# GecikmeliAnahtar.net
KiCad netlist of a schematic drawn in EAGLE
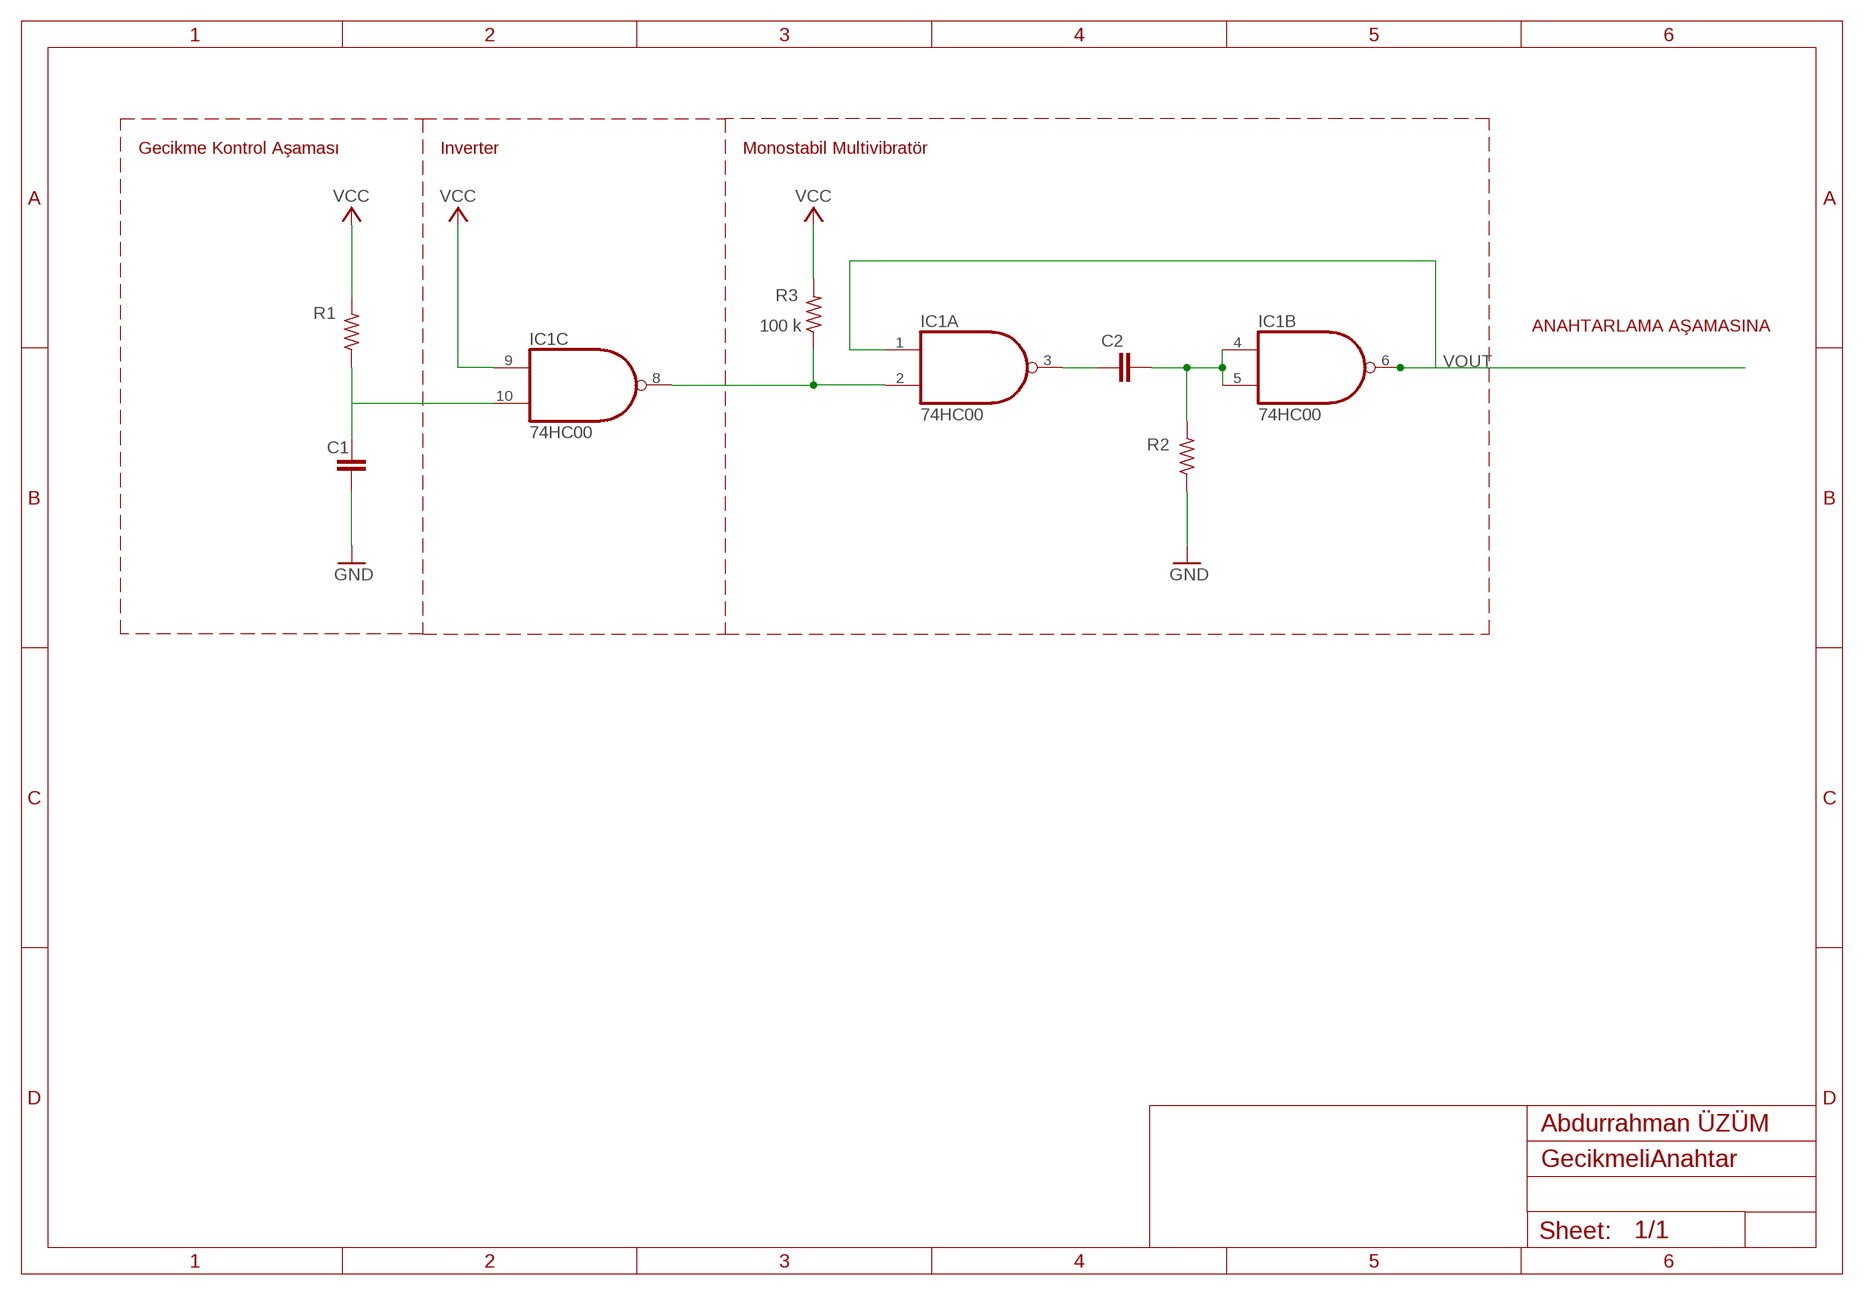
[diagram p0: schematic, sheet 1]

(export (version "E")
  (design (tool "Eeschema 10.0.6"))
  (components
    (comp (ref "C1")
      (value "C-EU025-025X050")
      (footprint "eagle-import:C025-025X050")
      (libsource (lib "eagle-import") (part "C-EU025-025X050"))
    )
    (comp (ref "C2")
      (value "C-EU025-025X050")
      (footprint "eagle-import:C025-025X050")
      (libsource (lib "eagle-import") (part "C-EU025-025X050"))
    )
    (comp (ref "IC1")
      (value "74HC00")
      (footprint "eagle-import:DIL14")
      (libsource (lib "eagle-import") (part "7400N"))
    )
    (comp (ref "R1")
      (value "R-US_0207/10")
      (footprint "eagle-import:0207_10")
      (libsource (lib "eagle-import") (part "R-US_0207/10"))
    )
    (comp (ref "R2")
      (value "R-US_0207/10")
      (footprint "eagle-import:0207_10")
      (libsource (lib "eagle-import") (part "R-US_0207/10"))
    )
    (comp (ref "R3")
      (value "100 k")
      (footprint "eagle-import:0207_10")
      (libsource (lib "eagle-import") (part "R-US_0207/10"))
    )
  )
  (nets
    (net (code "1") (name "/VOUT") (class "Default")
      (node (ref "IC1") (pin "1") (pinfunction "I0_1") (pintype "input"))
      (node (ref "IC1") (pin "6") (pinfunction "O_6") (pintype "output"))
    )
    (net (code "2") (name "GND") (class "Default")
      (node (ref "C1") (pin "2") (pinfunction "2_2") (pintype "passive"))
      (node (ref "R2") (pin "1") (pinfunction "1_1") (pintype "passive"))
    )
    (net (code "3") (name "Net-(IC1A-I1)") (class "Default")
      (node (ref "IC1") (pin "2") (pinfunction "I1_2") (pintype "input"))
      (node (ref "IC1") (pin "8") (pinfunction "O_8") (pintype "output"))
      (node (ref "R3") (pin "1") (pinfunction "1_1") (pintype "passive"))
    )
    (net (code "4") (name "Net-(IC1A-O)") (class "Default")
      (node (ref "C2") (pin "1") (pinfunction "1_1") (pintype "passive"))
      (node (ref "IC1") (pin "3") (pinfunction "O_3") (pintype "output"))
    )
    (net (code "5") (name "Net-(IC1B-I0)") (class "Default")
      (node (ref "C2") (pin "2") (pinfunction "2_2") (pintype "passive"))
      (node (ref "IC1") (pin "4") (pinfunction "I0_4") (pintype "input"))
      (node (ref "IC1") (pin "5") (pinfunction "I1_5") (pintype "input"))
      (node (ref "R2") (pin "2") (pinfunction "2_2") (pintype "passive"))
    )
    (net (code "6") (name "Net-(IC1C-I1)") (class "Default")
      (node (ref "C1") (pin "1") (pinfunction "1_1") (pintype "passive"))
      (node (ref "IC1") (pin "10") (pinfunction "I1_10") (pintype "input"))
      (node (ref "R1") (pin "1") (pinfunction "1_1") (pintype "passive"))
    )
    (net (code "7") (name "VCC") (class "Default")
      (node (ref "IC1") (pin "9") (pinfunction "I0_9") (pintype "input"))
      (node (ref "R1") (pin "2") (pinfunction "2_2") (pintype "passive"))
      (node (ref "R3") (pin "2") (pinfunction "2_2") (pintype "passive"))
    )
  )
)
